# SCH_URM07-Ultrasonic-Sensor_2025-04-24.net
KiCad netlist of a schematic drawn in EasyEDA
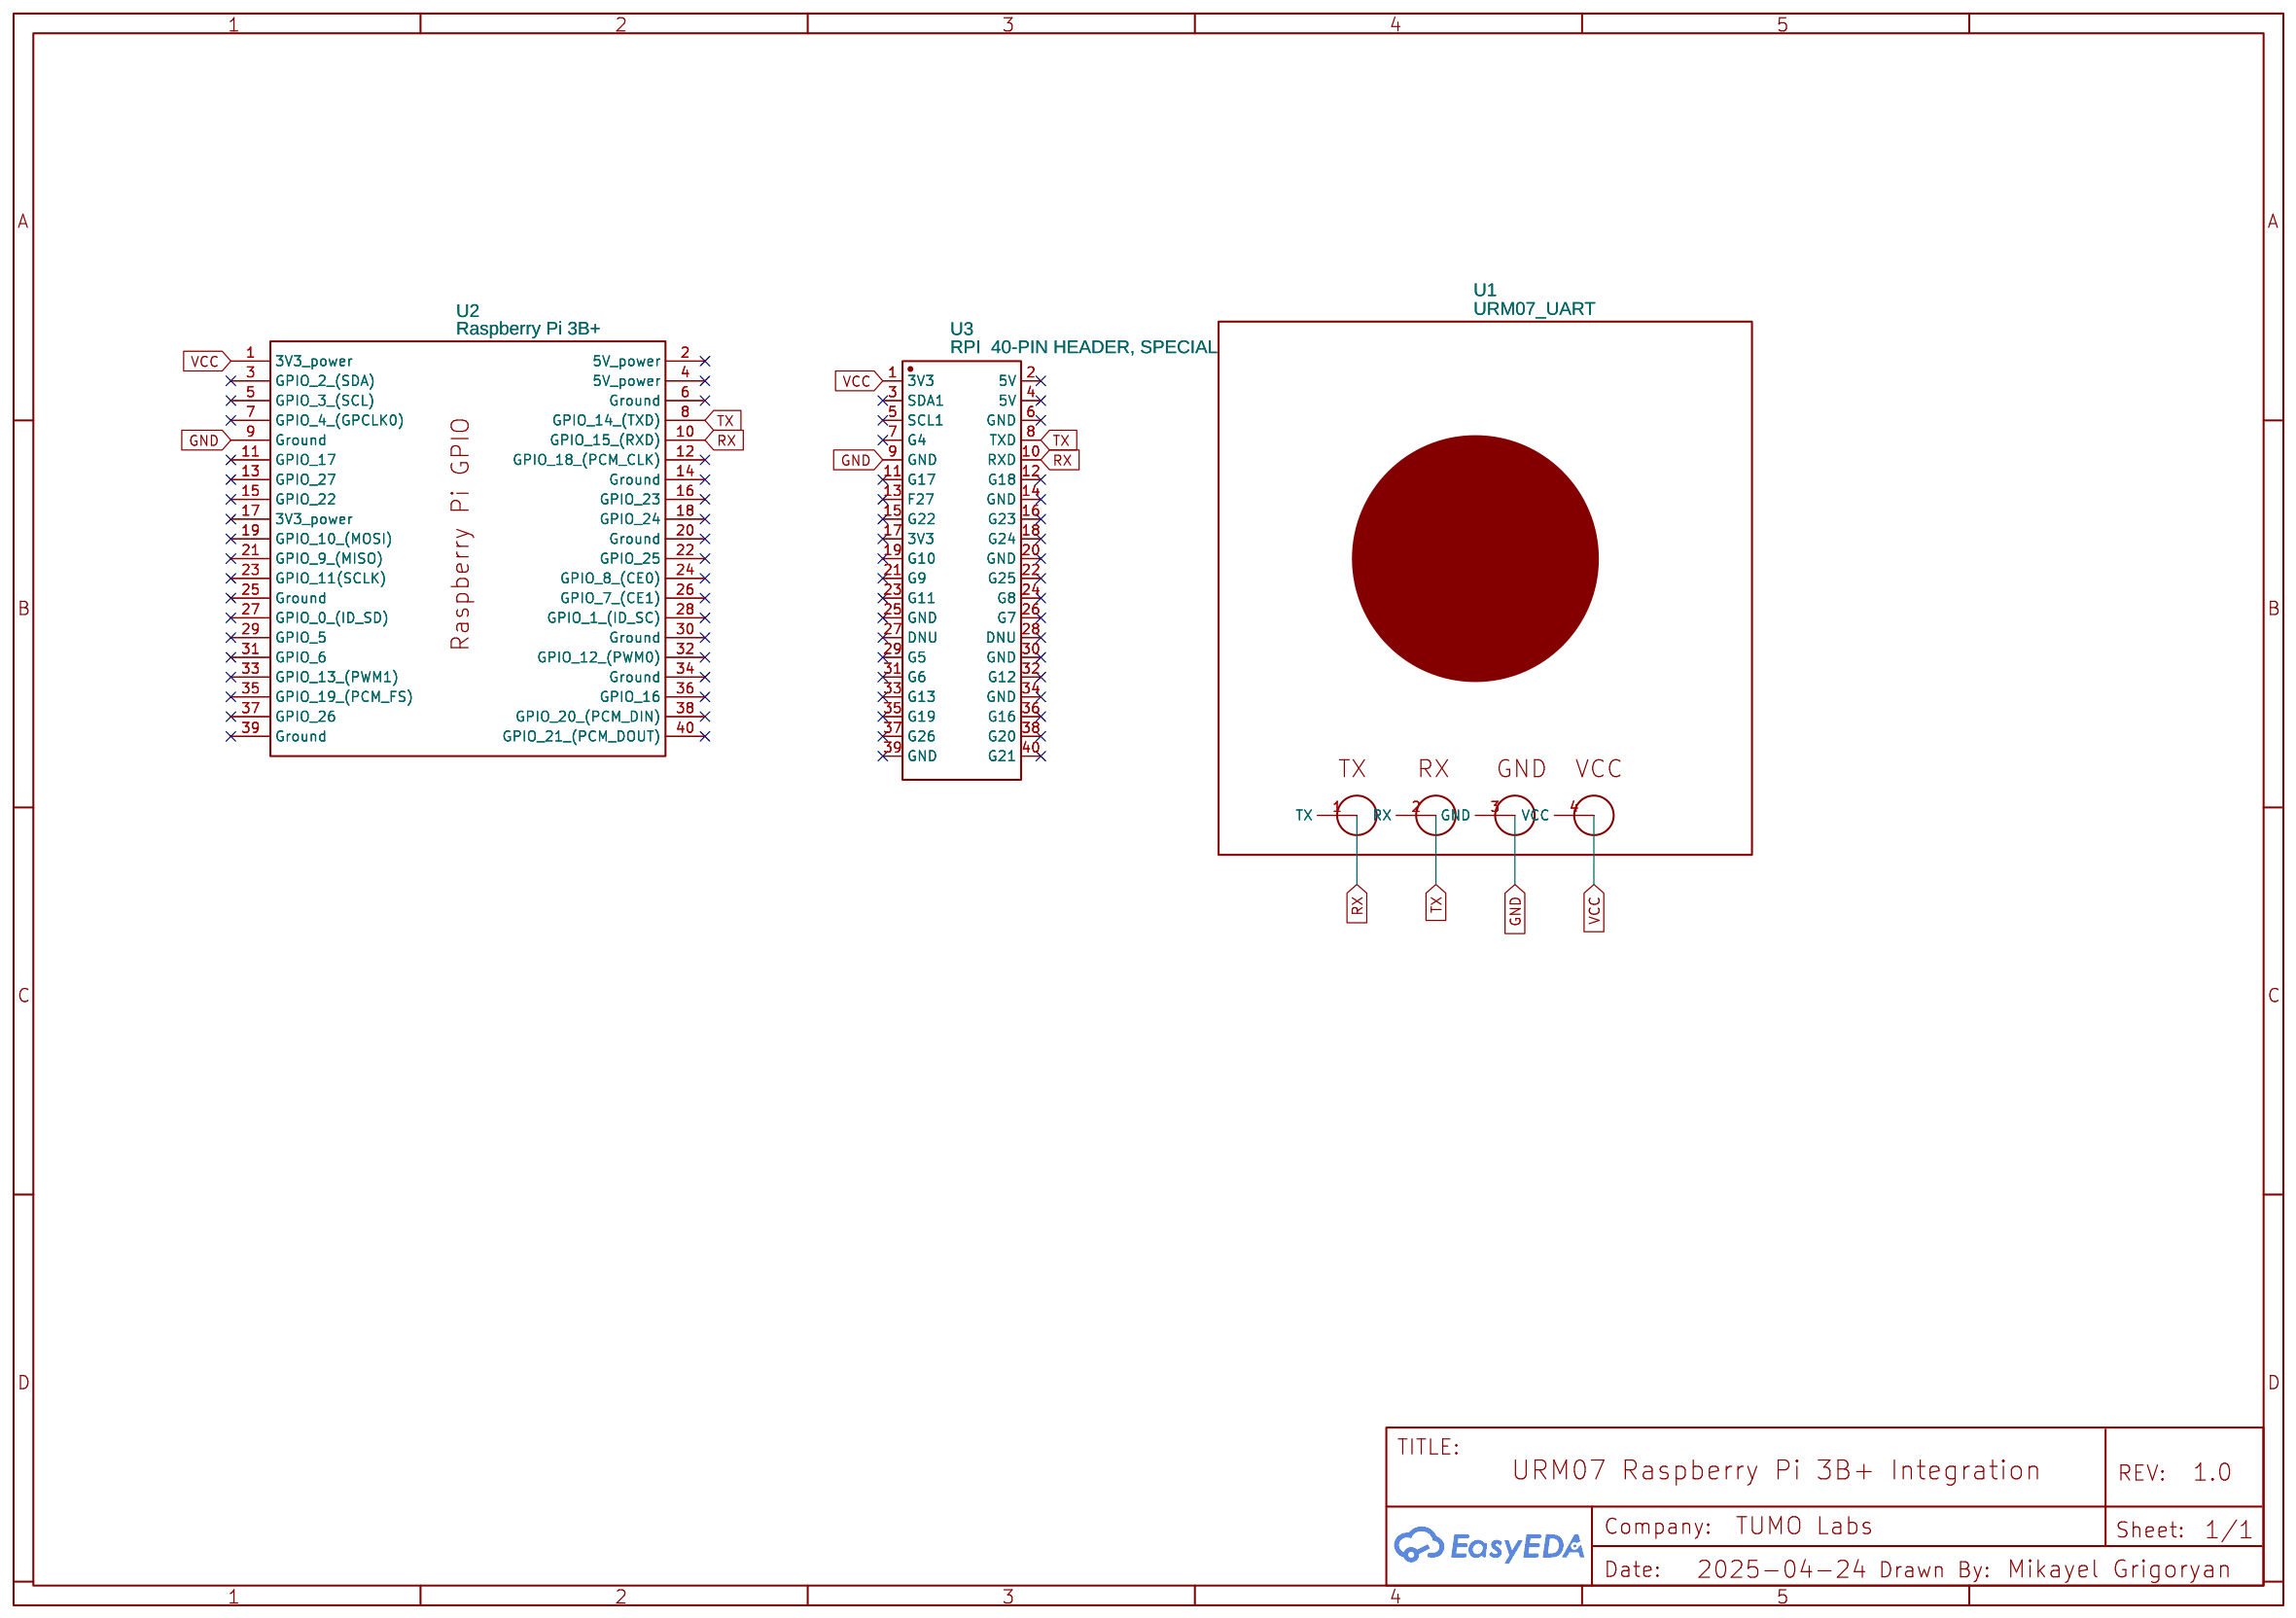
[diagram p0: schematic sheet]

(export (version "E")
  (design (tool "Eeschema 10.0.6"))
  (components
    (comp (ref "U1") (value "URM07_UART") (libsource (lib "") (part "URM07_UART")))
    (comp (ref "U2") (value "Raspberry Pi 3B+") (libsource (lib "") (part "Raspberry Pi 3B+")))
    (comp (ref "U3")
      (value "RPI  40-PIN HEADER, SPECIAL")
      (fields (field (name "Manufacturer Part") "RPi3B-GPIO"))
      (libsource (lib "") (part "RPI  40-PIN HEADER, SPECIAL"))
    )
  )
  (nets
    (net (code "1") (name "GND") (class "Default")
      (node (ref "U1") (pin "3") (pinfunction "GND_3") (pintype "unspecified"))
      (node (ref "U2") (pin "9") (pinfunction "Ground_9") (pintype "unspecified"))
      (node (ref "U3") (pin "9") (pinfunction "GND_9") (pintype "passive"))
    )
    (net (code "2") (name "RX") (class "Default")
      (node (ref "U1") (pin "1") (pinfunction "TX_1") (pintype "unspecified"))
      (node (ref "U2") (pin "10") (pinfunction "GPIO_15_(RXD)_10") (pintype "unspecified"))
      (node (ref "U3") (pin "10") (pinfunction "RXD_10") (pintype "bidirectional"))
    )
    (net (code "3") (name "TX") (class "Default")
      (node (ref "U1") (pin "2") (pinfunction "RX_2") (pintype "unspecified"))
      (node (ref "U2") (pin "8") (pinfunction "GPIO_14_(TXD)_8") (pintype "unspecified"))
      (node (ref "U3") (pin "8") (pinfunction "TXD_8") (pintype "passive"))
    )
    (net (code "4") (name "VCC") (class "Default")
      (node (ref "U1") (pin "4") (pinfunction "VCC_4") (pintype "unspecified"))
      (node (ref "U2") (pin "1") (pinfunction "3V3_power_1") (pintype "passive"))
      (node (ref "U3") (pin "1") (pinfunction "3V3_1") (pintype "passive"))
    )
    (net (code "5") (name "unconnected-(U2-3V3_power-Pad17)") (class "Default")
      (node (ref "U2") (pin "17") (pinfunction "3V3_power_17") (pintype "passive+no_connect"))
    )
    (net (code "6") (name "unconnected-(U2-5V_power-Pad2)") (class "Default")
      (node (ref "U2") (pin "2") (pinfunction "5V_power_2") (pintype "passive+no_connect"))
    )
    (net (code "7") (name "unconnected-(U2-5V_power-Pad4)") (class "Default")
      (node (ref "U2") (pin "4") (pinfunction "5V_power_4") (pintype "passive+no_connect"))
    )
    (net (code "8") (name "unconnected-(U2-GPIO_0_(ID_SD)-Pad27)") (class "Default")
      (node (ref "U2") (pin "27") (pinfunction "GPIO_0_(ID_SD)_27") (pintype "unspecified+no_connect"))
    )
    (net (code "9") (name "unconnected-(U2-GPIO_1_(ID_SC)-Pad28)") (class "Default")
      (node (ref "U2") (pin "28") (pinfunction "GPIO_1_(ID_SC)_28") (pintype "unspecified+no_connect"))
    )
    (net (code "10") (name "unconnected-(U2-GPIO_2_(SDA)-Pad3)") (class "Default")
      (node (ref "U2") (pin "3") (pinfunction "GPIO_2_(SDA)_3") (pintype "unspecified+no_connect"))
    )
    (net (code "11") (name "unconnected-(U2-GPIO_3_(SCL)-Pad5)") (class "Default")
      (node (ref "U2") (pin "5") (pinfunction "GPIO_3_(SCL)_5") (pintype "unspecified+no_connect"))
    )
    (net (code "12") (name "unconnected-(U2-GPIO_4_(GPCLK0)-Pad7)") (class "Default")
      (node (ref "U2") (pin "7") (pinfunction "GPIO_4_(GPCLK0)_7") (pintype "unspecified+no_connect"))
    )
    (net (code "13") (name "unconnected-(U2-GPIO_5-Pad29)") (class "Default")
      (node (ref "U2") (pin "29") (pinfunction "GPIO_5_29") (pintype "unspecified+no_connect"))
    )
    (net (code "14") (name "unconnected-(U2-GPIO_6-Pad31)") (class "Default")
      (node (ref "U2") (pin "31") (pinfunction "GPIO_6_31") (pintype "unspecified+no_connect"))
    )
    (net (code "15") (name "unconnected-(U2-GPIO_7_(CE1)-Pad26)") (class "Default")
      (node (ref "U2") (pin "26") (pinfunction "GPIO_7_(CE1)_26") (pintype "unspecified+no_connect"))
    )
    (net (code "16") (name "unconnected-(U2-GPIO_8_(CE0)-Pad24)") (class "Default")
      (node (ref "U2") (pin "24") (pinfunction "GPIO_8_(CE0)_24") (pintype "unspecified+no_connect"))
    )
    (net (code "17") (name "unconnected-(U2-GPIO_9_(MISO)-Pad21)") (class "Default")
      (node (ref "U2") (pin "21") (pinfunction "GPIO_9_(MISO)_21") (pintype "unspecified+no_connect"))
    )
    (net (code "18") (name "unconnected-(U2-GPIO_10_(MOSI)-Pad19)") (class "Default")
      (node (ref "U2") (pin "19") (pinfunction "GPIO_10_(MOSI)_19") (pintype "unspecified+no_connect"))
    )
    (net (code "19") (name "unconnected-(U2-GPIO_11(SCLK)-Pad23)") (class "Default")
      (node (ref "U2") (pin "23") (pinfunction "GPIO_11(SCLK)_23") (pintype "unspecified+no_connect"))
    )
    (net (code "20") (name "unconnected-(U2-GPIO_12_(PWM0)-Pad32)") (class "Default")
      (node (ref "U2") (pin "32") (pinfunction "GPIO_12_(PWM0)_32") (pintype "unspecified+no_connect"))
    )
    (net (code "21") (name "unconnected-(U2-GPIO_13_(PWM1)-Pad33)") (class "Default")
      (node (ref "U2") (pin "33") (pinfunction "GPIO_13_(PWM1)_33") (pintype "unspecified+no_connect"))
    )
    (net (code "22") (name "unconnected-(U2-GPIO_16-Pad36)") (class "Default")
      (node (ref "U2") (pin "36") (pinfunction "GPIO_16_36") (pintype "unspecified+no_connect"))
    )
    (net (code "23") (name "unconnected-(U2-GPIO_17-Pad11)") (class "Default")
      (node (ref "U2") (pin "11") (pinfunction "GPIO_17_11") (pintype "unspecified+no_connect"))
    )
    (net (code "24") (name "unconnected-(U2-GPIO_18_(PCM_CLK)-Pad12)") (class "Default")
      (node (ref "U2") (pin "12") (pinfunction "GPIO_18_(PCM_CLK)_12") (pintype "unspecified+no_connect"))
    )
    (net (code "25") (name "unconnected-(U2-GPIO_19_(PCM_FS)-Pad35)") (class "Default")
      (node (ref "U2") (pin "35") (pinfunction "GPIO_19_(PCM_FS)_35") (pintype "unspecified+no_connect"))
    )
    (net (code "26") (name "unconnected-(U2-GPIO_20_(PCM_DIN)-Pad38)") (class "Default")
      (node (ref "U2") (pin "38") (pinfunction "GPIO_20_(PCM_DIN)_38") (pintype "unspecified+no_connect"))
    )
    (net (code "27") (name "unconnected-(U2-GPIO_21_(PCM_DOUT)-Pad40)") (class "Default")
      (node (ref "U2") (pin "40") (pinfunction "GPIO_21_(PCM_DOUT)_40") (pintype "unspecified+no_connect"))
    )
    (net (code "28") (name "unconnected-(U2-GPIO_22-Pad15)") (class "Default")
      (node (ref "U2") (pin "15") (pinfunction "GPIO_22_15") (pintype "unspecified+no_connect"))
    )
    (net (code "29") (name "unconnected-(U2-GPIO_23-Pad16)") (class "Default")
      (node (ref "U2") (pin "16") (pinfunction "GPIO_23_16") (pintype "unspecified+no_connect"))
    )
    (net (code "30") (name "unconnected-(U2-GPIO_24-Pad18)") (class "Default")
      (node (ref "U2") (pin "18") (pinfunction "GPIO_24_18") (pintype "unspecified+no_connect"))
    )
    (net (code "31") (name "unconnected-(U2-GPIO_25-Pad22)") (class "Default")
      (node (ref "U2") (pin "22") (pinfunction "GPIO_25_22") (pintype "unspecified+no_connect"))
    )
    (net (code "32") (name "unconnected-(U2-GPIO_26-Pad37)") (class "Default")
      (node (ref "U2") (pin "37") (pinfunction "GPIO_26_37") (pintype "unspecified+no_connect"))
    )
    (net (code "33") (name "unconnected-(U2-GPIO_27-Pad13)") (class "Default")
      (node (ref "U2") (pin "13") (pinfunction "GPIO_27_13") (pintype "unspecified+no_connect"))
    )
    (net (code "34") (name "unconnected-(U2-Ground-Pad6)") (class "Default")
      (node (ref "U2") (pin "6") (pinfunction "Ground_6") (pintype "unspecified+no_connect"))
    )
    (net (code "35") (name "unconnected-(U2-Ground-Pad14)") (class "Default")
      (node (ref "U2") (pin "14") (pinfunction "Ground_14") (pintype "unspecified+no_connect"))
    )
    (net (code "36") (name "unconnected-(U2-Ground-Pad20)") (class "Default")
      (node (ref "U2") (pin "20") (pinfunction "Ground_20") (pintype "unspecified+no_connect"))
    )
    (net (code "37") (name "unconnected-(U2-Ground-Pad25)") (class "Default")
      (node (ref "U2") (pin "25") (pinfunction "Ground_25") (pintype "unspecified+no_connect"))
    )
    (net (code "38") (name "unconnected-(U2-Ground-Pad30)") (class "Default")
      (node (ref "U2") (pin "30") (pinfunction "Ground_30") (pintype "unspecified+no_connect"))
    )
    (net (code "39") (name "unconnected-(U2-Ground-Pad34)") (class "Default")
      (node (ref "U2") (pin "34") (pinfunction "Ground_34") (pintype "unspecified+no_connect"))
    )
    (net (code "40") (name "unconnected-(U2-Ground-Pad39)") (class "Default")
      (node (ref "U2") (pin "39") (pinfunction "Ground_39") (pintype "unspecified+no_connect"))
    )
    (net (code "41") (name "unconnected-(U3-3V3-Pad17)") (class "Default")
      (node (ref "U3") (pin "17") (pinfunction "3V3_17") (pintype "passive+no_connect"))
    )
    (net (code "42") (name "unconnected-(U3-5V-Pad2)") (class "Default")
      (node (ref "U3") (pin "2") (pinfunction "5V_2") (pintype "passive+no_connect"))
    )
    (net (code "43") (name "unconnected-(U3-5V-Pad4)") (class "Default")
      (node (ref "U3") (pin "4") (pinfunction "5V_4") (pintype "passive+no_connect"))
    )
    (net (code "44") (name "unconnected-(U3-DNU-Pad27)") (class "Default")
      (node (ref "U3") (pin "27") (pinfunction "DNU_27") (pintype "unspecified+no_connect"))
    )
    (net (code "45") (name "unconnected-(U3-DNU-Pad28)") (class "Default")
      (node (ref "U3") (pin "28") (pinfunction "DNU_28") (pintype "unspecified+no_connect"))
    )
    (net (code "46") (name "unconnected-(U3-F27-Pad13)") (class "Default")
      (node (ref "U3") (pin "13") (pinfunction "F27_13") (pintype "bidirectional+no_connect"))
    )
    (net (code "47") (name "unconnected-(U3-G4-Pad7)") (class "Default")
      (node (ref "U3") (pin "7") (pinfunction "G4_7") (pintype "bidirectional+no_connect"))
    )
    (net (code "48") (name "unconnected-(U3-G5-Pad29)") (class "Default")
      (node (ref "U3") (pin "29") (pinfunction "G5_29") (pintype "bidirectional+no_connect"))
    )
    (net (code "49") (name "unconnected-(U3-G6-Pad31)") (class "Default")
      (node (ref "U3") (pin "31") (pinfunction "G6_31") (pintype "bidirectional+no_connect"))
    )
    (net (code "50") (name "unconnected-(U3-G7-Pad26)") (class "Default")
      (node (ref "U3") (pin "26") (pinfunction "G7_26") (pintype "bidirectional+no_connect"))
    )
    (net (code "51") (name "unconnected-(U3-G8-Pad24)") (class "Default")
      (node (ref "U3") (pin "24") (pinfunction "G8_24") (pintype "bidirectional+no_connect"))
    )
    (net (code "52") (name "unconnected-(U3-G9-Pad21)") (class "Default")
      (node (ref "U3") (pin "21") (pinfunction "G9_21") (pintype "bidirectional+no_connect"))
    )
    (net (code "53") (name "unconnected-(U3-G10-Pad19)") (class "Default")
      (node (ref "U3") (pin "19") (pinfunction "G10_19") (pintype "bidirectional+no_connect"))
    )
    (net (code "54") (name "unconnected-(U3-G11-Pad23)") (class "Default")
      (node (ref "U3") (pin "23") (pinfunction "G11_23") (pintype "bidirectional+no_connect"))
    )
    (net (code "55") (name "unconnected-(U3-G12-Pad32)") (class "Default")
      (node (ref "U3") (pin "32") (pinfunction "G12_32") (pintype "bidirectional+no_connect"))
    )
    (net (code "56") (name "unconnected-(U3-G13-Pad33)") (class "Default")
      (node (ref "U3") (pin "33") (pinfunction "G13_33") (pintype "bidirectional+no_connect"))
    )
    (net (code "57") (name "unconnected-(U3-G16-Pad36)") (class "Default")
      (node (ref "U3") (pin "36") (pinfunction "G16_36") (pintype "bidirectional+no_connect"))
    )
    (net (code "58") (name "unconnected-(U3-G17-Pad11)") (class "Default")
      (node (ref "U3") (pin "11") (pinfunction "G17_11") (pintype "bidirectional+no_connect"))
    )
    (net (code "59") (name "unconnected-(U3-G18-Pad12)") (class "Default")
      (node (ref "U3") (pin "12") (pinfunction "G18_12") (pintype "bidirectional+no_connect"))
    )
    (net (code "60") (name "unconnected-(U3-G19-Pad35)") (class "Default")
      (node (ref "U3") (pin "35") (pinfunction "G19_35") (pintype "bidirectional+no_connect"))
    )
    (net (code "61") (name "unconnected-(U3-G20-Pad38)") (class "Default")
      (node (ref "U3") (pin "38") (pinfunction "G20_38") (pintype "bidirectional+no_connect"))
    )
    (net (code "62") (name "unconnected-(U3-G21-Pad40)") (class "Default")
      (node (ref "U3") (pin "40") (pinfunction "G21_40") (pintype "bidirectional+no_connect"))
    )
    (net (code "63") (name "unconnected-(U3-G22-Pad15)") (class "Default")
      (node (ref "U3") (pin "15") (pinfunction "G22_15") (pintype "output+no_connect"))
    )
    (net (code "64") (name "unconnected-(U3-G23-Pad16)") (class "Default")
      (node (ref "U3") (pin "16") (pinfunction "G23_16") (pintype "bidirectional+no_connect"))
    )
    (net (code "65") (name "unconnected-(U3-G24-Pad18)") (class "Default")
      (node (ref "U3") (pin "18") (pinfunction "G24_18") (pintype "bidirectional+no_connect"))
    )
    (net (code "66") (name "unconnected-(U3-G25-Pad22)") (class "Default")
      (node (ref "U3") (pin "22") (pinfunction "G25_22") (pintype "bidirectional+no_connect"))
    )
    (net (code "67") (name "unconnected-(U3-G26-Pad37)") (class "Default")
      (node (ref "U3") (pin "37") (pinfunction "G26_37") (pintype "bidirectional+no_connect"))
    )
    (net (code "68") (name "unconnected-(U3-GND-Pad6)") (class "Default")
      (node (ref "U3") (pin "6") (pinfunction "GND_6") (pintype "passive+no_connect"))
    )
    (net (code "69") (name "unconnected-(U3-GND-Pad14)") (class "Default")
      (node (ref "U3") (pin "14") (pinfunction "GND_14") (pintype "passive+no_connect"))
    )
    (net (code "70") (name "unconnected-(U3-GND-Pad20)") (class "Default")
      (node (ref "U3") (pin "20") (pinfunction "GND_20") (pintype "passive+no_connect"))
    )
    (net (code "71") (name "unconnected-(U3-GND-Pad25)") (class "Default")
      (node (ref "U3") (pin "25") (pinfunction "GND_25") (pintype "passive+no_connect"))
    )
    (net (code "72") (name "unconnected-(U3-GND-Pad30)") (class "Default")
      (node (ref "U3") (pin "30") (pinfunction "GND_30") (pintype "passive+no_connect"))
    )
    (net (code "73") (name "unconnected-(U3-GND-Pad34)") (class "Default")
      (node (ref "U3") (pin "34") (pinfunction "GND_34") (pintype "passive+no_connect"))
    )
    (net (code "74") (name "unconnected-(U3-GND-Pad39)") (class "Default")
      (node (ref "U3") (pin "39") (pinfunction "GND_39") (pintype "passive+no_connect"))
    )
    (net (code "75") (name "unconnected-(U3-SCL1-Pad5)") (class "Default")
      (node (ref "U3") (pin "5") (pinfunction "SCL1_5") (pintype "bidirectional+no_connect"))
    )
    (net (code "76") (name "unconnected-(U3-SDA1-Pad3)") (class "Default")
      (node (ref "U3") (pin "3") (pinfunction "SDA1_3") (pintype "bidirectional+no_connect"))
    )
  )
)
